# YOTSUBA_MC_ver_2_0.net
KiCad netlist of a schematic drawn in EAGLE
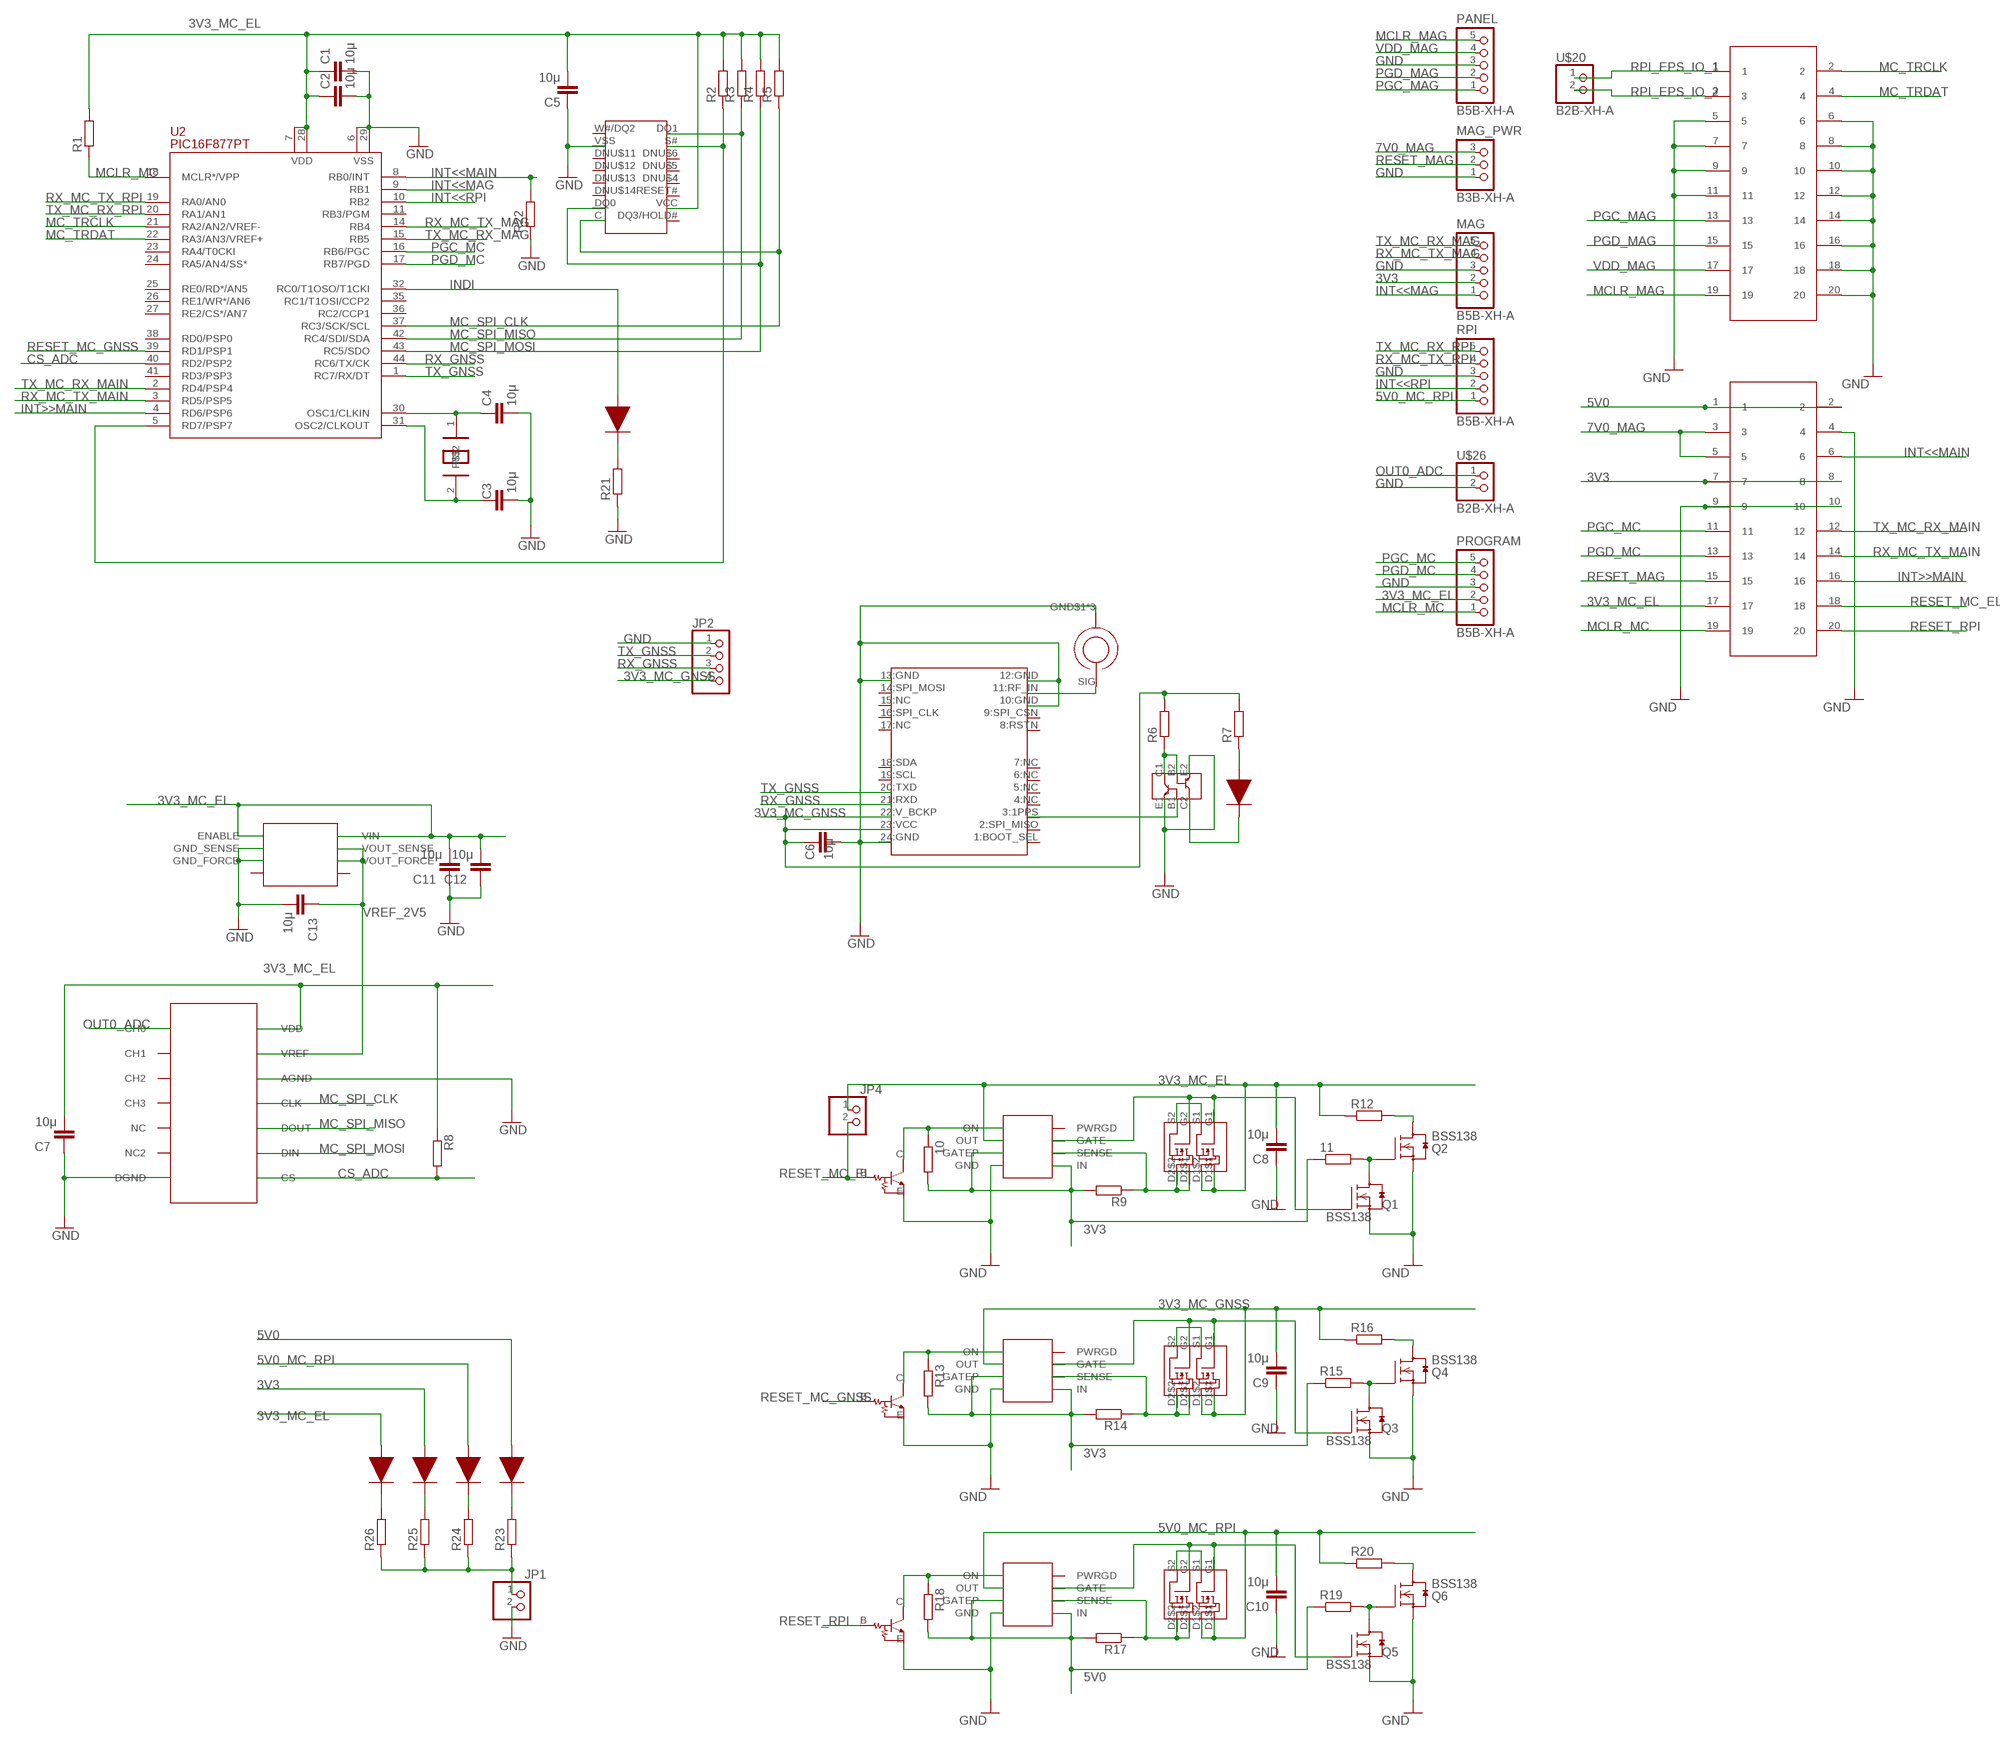
[diagram p0: schematic, sheet 1]

(export (version "E")
  (design (tool "Eeschema 10.0.6"))
  (components
    (comp (ref "10")
      (value "R-EU_M2012")
      (footprint "eagle-import:M2012")
      (libsource (lib "eagle-import") (part "R-EU_M2012"))
    )
    (comp (ref "11")
      (value "R-EU_M2012")
      (footprint "eagle-import:M2012")
      (libsource (lib "eagle-import") (part "R-EU_M2012"))
    )
    (comp (ref "C1")
      (value "10μ")
      (footprint "eagle-import:C2012")
      (libsource (lib "eagle-import") (part "C-EUC2012"))
    )
    (comp (ref "C2")
      (value "10μ")
      (footprint "eagle-import:C2012")
      (libsource (lib "eagle-import") (part "C-EUC2012"))
    )
    (comp (ref "C3")
      (value "10μ")
      (footprint "eagle-import:C2012")
      (libsource (lib "eagle-import") (part "C-EUC2012"))
    )
    (comp (ref "C4")
      (value "10μ")
      (footprint "eagle-import:C2012")
      (libsource (lib "eagle-import") (part "C-EUC2012"))
    )
    (comp (ref "C5")
      (value "10μ")
      (footprint "eagle-import:C2012")
      (libsource (lib "eagle-import") (part "C-EUC2012"))
    )
    (comp (ref "C6")
      (value "10μ")
      (footprint "eagle-import:C2012")
      (libsource (lib "eagle-import") (part "C-EUC2012"))
    )
    (comp (ref "C7")
      (value "10μ")
      (footprint "eagle-import:C2012")
      (libsource (lib "eagle-import") (part "C-EUC2012"))
    )
    (comp (ref "C8")
      (value "10μ")
      (footprint "eagle-import:C2012")
      (libsource (lib "eagle-import") (part "C-EUC2012"))
    )
    (comp (ref "C9")
      (value "10μ")
      (footprint "eagle-import:C2012")
      (libsource (lib "eagle-import") (part "C-EUC2012"))
    )
    (comp (ref "C10")
      (value "10μ")
      (footprint "eagle-import:C2012")
      (libsource (lib "eagle-import") (part "C-EUC2012"))
    )
    (comp (ref "C11")
      (value "10μ")
      (footprint "eagle-import:C2012")
      (libsource (lib "eagle-import") (part "C-EUC2012"))
    )
    (comp (ref "C12")
      (value "10μ")
      (footprint "eagle-import:C2012")
      (libsource (lib "eagle-import") (part "C-EUC2012"))
    )
    (comp (ref "C13")
      (value "10μ")
      (footprint "eagle-import:C2012")
      (libsource (lib "eagle-import") (part "C-EUC2012"))
    )
    (comp (ref "CLK1")
      (value "HC49/4H")
      (footprint "eagle-import:HC49_4H")
      (libsource (lib "eagle-import") (part "HC49/4H"))
    )
    (comp (ref "JP1")
      (value "PINHD-1X2")
      (footprint "eagle-import:1X02")
      (libsource (lib "eagle-import") (part "PINHD-1X2"))
    )
    (comp (ref "JP2")
      (value "PINHD-1X4")
      (footprint "eagle-import:1X04")
      (libsource (lib "eagle-import") (part "PINHD-1X4"))
    )
    (comp (ref "JP4")
      (value "PINHD-1X2")
      (footprint "eagle-import:1X02")
      (libsource (lib "eagle-import") (part "PINHD-1X2"))
    )
    (comp (ref "MAG")
      (value "B5B-XH-A")
      (footprint "eagle-import:B5B-XH-A")
      (libsource (lib "eagle-import") (part "B5B-XH-A"))
    )
    (comp (ref "MAG_PWR")
      (value "B3B-XH-A")
      (footprint "eagle-import:B3B-XH-A")
      (libsource (lib "eagle-import") (part "B3B-XH-A"))
    )
    (comp (ref "PANEL")
      (value "B5B-XH-A")
      (footprint "eagle-import:B5B-XH-A")
      (libsource (lib "eagle-import") (part "B5B-XH-A"))
    )
    (comp (ref "PROGRAM")
      (value "B5B-XH-A")
      (footprint "eagle-import:B5B-XH-A")
      (libsource (lib "eagle-import") (part "B5B-XH-A"))
    )
    (comp (ref "Q1")
      (value "BSS138")
      (footprint "eagle-import:SOT23")
      (libsource (lib "eagle-import") (part "BSS138"))
    )
    (comp (ref "Q2")
      (value "BSS138")
      (footprint "eagle-import:SOT23")
      (libsource (lib "eagle-import") (part "BSS138"))
    )
    (comp (ref "Q3")
      (value "BSS138")
      (footprint "eagle-import:SOT23")
      (libsource (lib "eagle-import") (part "BSS138"))
    )
    (comp (ref "Q4")
      (value "BSS138")
      (footprint "eagle-import:SOT23")
      (libsource (lib "eagle-import") (part "BSS138"))
    )
    (comp (ref "Q5")
      (value "BSS138")
      (footprint "eagle-import:SOT23")
      (libsource (lib "eagle-import") (part "BSS138"))
    )
    (comp (ref "Q6")
      (value "BSS138")
      (footprint "eagle-import:SOT23")
      (libsource (lib "eagle-import") (part "BSS138"))
    )
    (comp (ref "R1")
      (value "R-EU_M2012")
      (footprint "eagle-import:M2012")
      (libsource (lib "eagle-import") (part "R-EU_M2012"))
    )
    (comp (ref "R2")
      (value "R-EU_M2012")
      (footprint "eagle-import:M2012")
      (libsource (lib "eagle-import") (part "R-EU_M2012"))
    )
    (comp (ref "R3")
      (value "R-EU_M2012")
      (footprint "eagle-import:M2012")
      (libsource (lib "eagle-import") (part "R-EU_M2012"))
    )
    (comp (ref "R4")
      (value "R-EU_M2012")
      (footprint "eagle-import:M2012")
      (libsource (lib "eagle-import") (part "R-EU_M2012"))
    )
    (comp (ref "R5")
      (value "R-EU_M2012")
      (footprint "eagle-import:M2012")
      (libsource (lib "eagle-import") (part "R-EU_M2012"))
    )
    (comp (ref "R6")
      (value "R-EU_M2012")
      (footprint "eagle-import:M2012")
      (libsource (lib "eagle-import") (part "R-EU_M2012"))
    )
    (comp (ref "R7")
      (value "R-EU_M2012")
      (footprint "eagle-import:M2012")
      (libsource (lib "eagle-import") (part "R-EU_M2012"))
    )
    (comp (ref "R8")
      (value "R-EU_M2012")
      (footprint "eagle-import:M2012")
      (libsource (lib "eagle-import") (part "R-EU_M2012"))
    )
    (comp (ref "R9")
      (value "R-EU_M2012")
      (footprint "eagle-import:M2012")
      (libsource (lib "eagle-import") (part "R-EU_M2012"))
    )
    (comp (ref "R12")
      (value "R-EU_M2012")
      (footprint "eagle-import:M2012")
      (libsource (lib "eagle-import") (part "R-EU_M2012"))
    )
    (comp (ref "R13")
      (value "R-EU_M2012")
      (footprint "eagle-import:M2012")
      (libsource (lib "eagle-import") (part "R-EU_M2012"))
    )
    (comp (ref "R14")
      (value "R-EU_M2012")
      (footprint "eagle-import:M2012")
      (libsource (lib "eagle-import") (part "R-EU_M2012"))
    )
    (comp (ref "R15")
      (value "R-EU_M2012")
      (footprint "eagle-import:M2012")
      (libsource (lib "eagle-import") (part "R-EU_M2012"))
    )
    (comp (ref "R16")
      (value "R-EU_M2012")
      (footprint "eagle-import:M2012")
      (libsource (lib "eagle-import") (part "R-EU_M2012"))
    )
    (comp (ref "R17")
      (value "R-EU_M2012")
      (footprint "eagle-import:M2012")
      (libsource (lib "eagle-import") (part "R-EU_M2012"))
    )
    (comp (ref "R18")
      (value "R-EU_M2012")
      (footprint "eagle-import:M2012")
      (libsource (lib "eagle-import") (part "R-EU_M2012"))
    )
    (comp (ref "R19")
      (value "R-EU_M2012")
      (footprint "eagle-import:M2012")
      (libsource (lib "eagle-import") (part "R-EU_M2012"))
    )
    (comp (ref "R20")
      (value "R-EU_M2012")
      (footprint "eagle-import:M2012")
      (libsource (lib "eagle-import") (part "R-EU_M2012"))
    )
    (comp (ref "R21")
      (value "R-EU_M2012")
      (footprint "eagle-import:M2012")
      (libsource (lib "eagle-import") (part "R-EU_M2012"))
    )
    (comp (ref "R22")
      (value "R-EU_M2012")
      (footprint "eagle-import:M2012")
      (libsource (lib "eagle-import") (part "R-EU_M2012"))
    )
    (comp (ref "R23")
      (value "R-EU_M2012")
      (footprint "eagle-import:M2012")
      (libsource (lib "eagle-import") (part "R-EU_M2012"))
    )
    (comp (ref "R24")
      (value "R-EU_M2012")
      (footprint "eagle-import:M2012")
      (libsource (lib "eagle-import") (part "R-EU_M2012"))
    )
    (comp (ref "R25")
      (value "R-EU_M2012")
      (footprint "eagle-import:M2012")
      (libsource (lib "eagle-import") (part "R-EU_M2012"))
    )
    (comp (ref "R26")
      (value "R-EU_M2012")
      (footprint "eagle-import:M2012")
      (libsource (lib "eagle-import") (part "R-EU_M2012"))
    )
    (comp (ref "RPI")
      (value "B5B-XH-A")
      (footprint "eagle-import:B5B-XH-A")
      (libsource (lib "eagle-import") (part "B5B-XH-A"))
    )
    (comp (ref "U$1")
      (value "MT25QL512_16SOP2")
      (footprint "eagle-import:SOIC127P1032X265-16N")
      (libsource (lib "eagle-import") (part "MT25QL512_16SOP2"))
    )
    (comp (ref "U$2")
      (value "ORION_B16")
      (footprint "eagle-import:ORION_B16")
      (libsource (lib "eagle-import") (part "ORION_B16"))
    )
    (comp (ref "U$3")
      (value "HN1C01FU")
      (footprint "eagle-import:SOT65P210X100-6N")
      (libsource (lib "eagle-import") (part "HN1C01FU"))
    )
    (comp (ref "U$4")
      (value "LED_1608")
      (footprint "eagle-import:LED_1608")
      (libsource (lib "eagle-import") (part "LED_1608"))
    )
    (comp (ref "U$5")
      (value "U.FL-R")
      (footprint "eagle-import:U.FL-R")
      (libsource (lib "eagle-import") (part "U.FL-R"))
    )
    (comp (ref "U$6")
      (value "MCP3204_S")
      (footprint "eagle-import:MCP3204_S")
      (libsource (lib "eagle-import") (part "MCP3204_S"))
    )
    (comp (ref "U$7")
      (value "DMG6898LSD")
      (footprint "eagle-import:SOIC127P600X150-8N")
      (libsource (lib "eagle-import") (part "DMG6898LSD"))
    )
    (comp (ref "U$8")
      (value "LTC4361")
      (footprint "eagle-import:SOP65P280X100-8N")
      (libsource (lib "eagle-import") (part "LTC4361"))
    )
    (comp (ref "U$9")
      (value "DTC144EKA")
      (footprint "eagle-import:SOT-346")
      (libsource (lib "eagle-import") (part "DTC144EKA"))
    )
    (comp (ref "U$10")
      (value "DMG6898LSD")
      (footprint "eagle-import:SOIC127P600X150-8N")
      (libsource (lib "eagle-import") (part "DMG6898LSD"))
    )
    (comp (ref "U$11")
      (value "LTC4361")
      (footprint "eagle-import:SOP65P280X100-8N")
      (libsource (lib "eagle-import") (part "LTC4361"))
    )
    (comp (ref "U$12")
      (value "DTC144EKA")
      (footprint "eagle-import:SOT-346")
      (libsource (lib "eagle-import") (part "DTC144EKA"))
    )
    (comp (ref "U$13")
      (value "DMG6898LSD")
      (footprint "eagle-import:SOIC127P600X150-8N")
      (libsource (lib "eagle-import") (part "DMG6898LSD"))
    )
    (comp (ref "U$14")
      (value "LTC4361")
      (footprint "eagle-import:SOP65P280X100-8N")
      (libsource (lib "eagle-import") (part "LTC4361"))
    )
    (comp (ref "U$15")
      (value "DTC144EKA")
      (footprint "eagle-import:SOT-346")
      (libsource (lib "eagle-import") (part "DTC144EKA"))
    )
    (comp (ref "U$17")
      (value "M50-3001045")
      (footprint "eagle-import:M50-3001045")
      (libsource (lib "eagle-import") (part "M50-3001045"))
    )
    (comp (ref "U$18")
      (value "LED_1608")
      (footprint "eagle-import:LED_1608")
      (libsource (lib "eagle-import") (part "LED_1608"))
    )
    (comp (ref "U$19")
      (value "ADR35XX")
      (footprint "eagle-import:SOP65P490X110-8N")
      (libsource (lib "eagle-import") (part "ADR35XX"))
    )
    (comp (ref "U$20")
      (value "B2B-XH-A")
      (footprint "eagle-import:B2B-XH-A")
      (libsource (lib "eagle-import") (part "B2B-XH-A"))
    )
    (comp (ref "U$21")
      (value "LED_1608")
      (footprint "eagle-import:LED_1608")
      (libsource (lib "eagle-import") (part "LED_1608"))
    )
    (comp (ref "U$22")
      (value "M50-3001045")
      (footprint "eagle-import:M50-3001045")
      (libsource (lib "eagle-import") (part "M50-3001045"))
    )
    (comp (ref "U$23")
      (value "LED_1608")
      (footprint "eagle-import:LED_1608")
      (libsource (lib "eagle-import") (part "LED_1608"))
    )
    (comp (ref "U$24")
      (value "LED_1608")
      (footprint "eagle-import:LED_1608")
      (libsource (lib "eagle-import") (part "LED_1608"))
    )
    (comp (ref "U$25")
      (value "LED_1608")
      (footprint "eagle-import:LED_1608")
      (libsource (lib "eagle-import") (part "LED_1608"))
    )
    (comp (ref "U$26")
      (value "B2B-XH-A")
      (footprint "eagle-import:B2B-XH-A")
      (libsource (lib "eagle-import") (part "B2B-XH-A"))
    )
    (comp (ref "U2")
      (value "PIC16F877PT")
      (footprint "eagle-import:TQFP44")
      (libsource (lib "eagle-import") (part "PIC16F877PT"))
    )
  )
  (nets
    (net (code "1") (name "/3V3") (class "Default")
      (node (ref "10") (pin "2") (pinfunction "2_2") (pintype "passive"))
      (node (ref "11") (pin "1") (pinfunction "1_1") (pintype "passive"))
      (node (ref "MAG") (pin "2") (pinfunction "2_2") (pintype "passive"))
      (node (ref "R13") (pin "2") (pinfunction "2_2") (pintype "passive"))
      (node (ref "R14") (pin "2") (pinfunction "2_2") (pintype "passive"))
      (node (ref "R15") (pin "1") (pinfunction "1_1") (pintype "passive"))
      (node (ref "R9") (pin "2") (pinfunction "2_2") (pintype "passive"))
      (node (ref "U$11") (pin "GATEP") (pinfunction "GATEP_GATEP") (pintype "bidirectional"))
      (node (ref "U$11") (pin "IN") (pinfunction "IN_IN") (pintype "bidirectional"))
      (node (ref "U$17") (pin "7") (pinfunction "7_7") (pintype "bidirectional"))
      (node (ref "U$17") (pin "8") (pinfunction "8_8") (pintype "bidirectional"))
      (node (ref "U$24") (pin "A") (pinfunction "A_A") (pintype "bidirectional"))
      (node (ref "U$8") (pin "GATEP") (pinfunction "GATEP_GATEP") (pintype "bidirectional"))
      (node (ref "U$8") (pin "IN") (pinfunction "IN_IN") (pintype "bidirectional"))
    )
    (net (code "2") (name "/3V3_MC_EL") (class "Default")
      (node (ref "C1") (pin "1") (pinfunction "1_1") (pintype "passive"))
      (node (ref "C11") (pin "2") (pinfunction "2_2") (pintype "passive"))
      (node (ref "C12") (pin "2") (pinfunction "2_2") (pintype "passive"))
      (node (ref "C2") (pin "1") (pinfunction "1_1") (pintype "passive"))
      (node (ref "C5") (pin "2") (pinfunction "2_2") (pintype "passive"))
      (node (ref "C7") (pin "2") (pinfunction "2_2") (pintype "passive"))
      (node (ref "C8") (pin "2") (pinfunction "2_2") (pintype "passive"))
      (node (ref "JP4") (pin "1") (pinfunction "1_1") (pintype "passive"))
      (node (ref "PROGRAM") (pin "2") (pinfunction "2_2") (pintype "passive"))
      (node (ref "R1") (pin "2") (pinfunction "2_2") (pintype "passive"))
      (node (ref "R12") (pin "1") (pinfunction "1_1") (pintype "passive"))
      (node (ref "R2") (pin "2") (pinfunction "2_2") (pintype "passive"))
      (node (ref "R3") (pin "2") (pinfunction "2_2") (pintype "passive"))
      (node (ref "R4") (pin "2") (pinfunction "2_2") (pintype "passive"))
      (node (ref "R5") (pin "2") (pinfunction "2_2") (pintype "passive"))
      (node (ref "R8") (pin "1") (pinfunction "1_1") (pintype "passive"))
      (node (ref "U$1") (pin "VCC") (pinfunction "VCC_VCC") (pintype "bidirectional"))
      (node (ref "U$17") (pin "17") (pinfunction "17_17") (pintype "bidirectional"))
      (node (ref "U$19") (pin "ENABLE") (pinfunction "ENABLE_ENABLE") (pintype "bidirectional"))
      (node (ref "U$19") (pin "VIN") (pinfunction "VIN_VIN") (pintype "bidirectional"))
      (node (ref "U$25") (pin "A") (pinfunction "A_A") (pintype "bidirectional"))
      (node (ref "U$6") (pin "VDD") (pinfunction "VDD_VDD") (pintype "bidirectional"))
      (node (ref "U$7") (pin "D1$1") (pinfunction "D1$1_D1$1") (pintype "bidirectional"))
      (node (ref "U$7") (pin "D1$2") (pinfunction "D1$2_D1$2") (pintype "bidirectional"))
      (node (ref "U$8") (pin "OUT") (pinfunction "OUT_OUT") (pintype "bidirectional"))
      (node (ref "U2") (pin "28") (pinfunction "VDD_28") (pintype "bidirectional"))
      (node (ref "U2") (pin "7") (pinfunction "VDD_7") (pintype "bidirectional"))
    )
    (net (code "3") (name "/3V3_MC_GNSS") (class "Default")
      (node (ref "C6") (pin "1") (pinfunction "1_1") (pintype "passive"))
      (node (ref "C9") (pin "2") (pinfunction "2_2") (pintype "passive"))
      (node (ref "JP2") (pin "4") (pinfunction "4_4") (pintype "passive"))
      (node (ref "R16") (pin "1") (pinfunction "1_1") (pintype "passive"))
      (node (ref "R6") (pin "2") (pinfunction "2_2") (pintype "passive"))
      (node (ref "R7") (pin "2") (pinfunction "2_2") (pintype "passive"))
      (node (ref "U$10") (pin "D1$1") (pinfunction "D1$1_D1$1") (pintype "bidirectional"))
      (node (ref "U$10") (pin "D1$2") (pinfunction "D1$2_D1$2") (pintype "bidirectional"))
      (node (ref "U$11") (pin "OUT") (pinfunction "OUT_OUT") (pintype "bidirectional"))
      (node (ref "U$2") (pin "22:V_BCKP") (pinfunction "22:V_BCKP_22:V_BCKP") (pintype "bidirectional"))
      (node (ref "U$2") (pin "23:VCC") (pinfunction "23:VCC_23:VCC") (pintype "bidirectional"))
    )
    (net (code "4") (name "/5V0") (class "Default")
      (node (ref "R17") (pin "2") (pinfunction "2_2") (pintype "passive"))
      (node (ref "R18") (pin "2") (pinfunction "2_2") (pintype "passive"))
      (node (ref "R19") (pin "1") (pinfunction "1_1") (pintype "passive"))
      (node (ref "U$14") (pin "GATEP") (pinfunction "GATEP_GATEP") (pintype "bidirectional"))
      (node (ref "U$14") (pin "IN") (pinfunction "IN_IN") (pintype "bidirectional"))
      (node (ref "U$17") (pin "1") (pinfunction "1_1") (pintype "bidirectional"))
      (node (ref "U$17") (pin "2") (pinfunction "2_2") (pintype "bidirectional"))
      (node (ref "U$21") (pin "A") (pinfunction "A_A") (pintype "bidirectional"))
    )
    (net (code "5") (name "/5V0_MC_RPI") (class "Default")
      (node (ref "C10") (pin "2") (pinfunction "2_2") (pintype "passive"))
      (node (ref "R20") (pin "1") (pinfunction "1_1") (pintype "passive"))
      (node (ref "RPI") (pin "1") (pinfunction "1_1") (pintype "passive"))
      (node (ref "U$13") (pin "D1$1") (pinfunction "D1$1_D1$1") (pintype "bidirectional"))
      (node (ref "U$13") (pin "D1$2") (pinfunction "D1$2_D1$2") (pintype "bidirectional"))
      (node (ref "U$14") (pin "OUT") (pinfunction "OUT_OUT") (pintype "bidirectional"))
      (node (ref "U$23") (pin "A") (pinfunction "A_A") (pintype "bidirectional"))
    )
    (net (code "6") (name "/7V0_MAG") (class "Default")
      (node (ref "MAG_PWR") (pin "3") (pinfunction "3_3") (pintype "passive"))
      (node (ref "U$17") (pin "3") (pinfunction "3_3") (pintype "bidirectional"))
      (node (ref "U$17") (pin "5") (pinfunction "5_5") (pintype "bidirectional"))
    )
    (net (code "7") (name "/CS_ADC") (class "Default")
      (node (ref "R8") (pin "2") (pinfunction "2_2") (pintype "passive"))
      (node (ref "U$6") (pin "CS") (pinfunction "CS_CS") (pintype "bidirectional"))
      (node (ref "U2") (pin "40") (pinfunction "RD2/PSP2_40") (pintype "bidirectional"))
    )
    (net (code "8") (name "/INDI") (class "Default")
      (node (ref "U$18") (pin "A") (pinfunction "A_A") (pintype "bidirectional"))
      (node (ref "U2") (pin "32") (pinfunction "RC0/T1OSO/T1CKI_32") (pintype "bidirectional"))
    )
    (net (code "9") (name "/INT<<MAG") (class "Default")
      (node (ref "MAG") (pin "1") (pinfunction "1_1") (pintype "passive"))
      (node (ref "U2") (pin "9") (pinfunction "RB1_9") (pintype "bidirectional"))
    )
    (net (code "10") (name "/INT<<MAIN") (class "Default")
      (node (ref "R22") (pin "2") (pinfunction "2_2") (pintype "passive"))
      (node (ref "U$17") (pin "6") (pinfunction "6_6") (pintype "bidirectional"))
      (node (ref "U2") (pin "8") (pinfunction "RB0/INT_8") (pintype "bidirectional"))
    )
    (net (code "11") (name "/INT<<RPI") (class "Default")
      (node (ref "RPI") (pin "2") (pinfunction "2_2") (pintype "passive"))
      (node (ref "U2") (pin "10") (pinfunction "RB2_10") (pintype "bidirectional"))
    )
    (net (code "12") (name "/INT>>MAIN") (class "Default")
      (node (ref "U$17") (pin "16") (pinfunction "16_16") (pintype "bidirectional"))
      (node (ref "U2") (pin "4") (pinfunction "RD6/PSP6_4") (pintype "bidirectional"))
    )
    (net (code "13") (name "/MCLR_MAG") (class "Default")
      (node (ref "PANEL") (pin "5") (pinfunction "5_5") (pintype "passive"))
      (node (ref "U$22") (pin "19") (pinfunction "19_19") (pintype "bidirectional"))
    )
    (net (code "14") (name "/MCLR_MC") (class "Default")
      (node (ref "PROGRAM") (pin "1") (pinfunction "1_1") (pintype "passive"))
      (node (ref "R1") (pin "1") (pinfunction "1_1") (pintype "passive"))
      (node (ref "U$17") (pin "19") (pinfunction "19_19") (pintype "bidirectional"))
      (node (ref "U2") (pin "18") (pinfunction "MCLR*/VPP_18") (pintype "input"))
    )
    (net (code "15") (name "/MC_SPI_CLK") (class "Default")
      (node (ref "R5") (pin "1") (pinfunction "1_1") (pintype "passive"))
      (node (ref "U$1") (pin "C") (pinfunction "C_C") (pintype "bidirectional"))
      (node (ref "U$6") (pin "CLK") (pinfunction "CLK_CLK") (pintype "bidirectional"))
      (node (ref "U2") (pin "37") (pinfunction "RC3/SCK/SCL_37") (pintype "bidirectional"))
    )
    (net (code "16") (name "/MC_SPI_MISO") (class "Default")
      (node (ref "R3") (pin "1") (pinfunction "1_1") (pintype "passive"))
      (node (ref "U$1") (pin "DQ1") (pinfunction "DQ1_DQ1") (pintype "bidirectional"))
      (node (ref "U$6") (pin "DOUT") (pinfunction "DOUT_DOUT") (pintype "bidirectional"))
      (node (ref "U2") (pin "42") (pinfunction "RC4/SDI/SDA_42") (pintype "bidirectional"))
    )
    (net (code "17") (name "/MC_SPI_MOSI") (class "Default")
      (node (ref "R4") (pin "1") (pinfunction "1_1") (pintype "passive"))
      (node (ref "U$1") (pin "DQ0") (pinfunction "DQ0_DQ0") (pintype "bidirectional"))
      (node (ref "U$6") (pin "DIN") (pinfunction "DIN_DIN") (pintype "bidirectional"))
      (node (ref "U2") (pin "43") (pinfunction "RC5/SDO_43") (pintype "bidirectional"))
    )
    (net (code "18") (name "/MC_TRCLK") (class "Default")
      (node (ref "U$22") (pin "2") (pinfunction "2_2") (pintype "bidirectional"))
      (node (ref "U2") (pin "21") (pinfunction "RA2/AN2/VREF-_21") (pintype "bidirectional"))
    )
    (net (code "19") (name "/MC_TRDAT") (class "Default")
      (node (ref "U$22") (pin "4") (pinfunction "4_4") (pintype "bidirectional"))
      (node (ref "U2") (pin "22") (pinfunction "RA3/AN3/VREF+_22") (pintype "bidirectional"))
    )
    (net (code "20") (name "/OUT0_ADC") (class "Default")
      (node (ref "U$26") (pin "1") (pinfunction "1_1") (pintype "passive"))
      (node (ref "U$6") (pin "CH0") (pinfunction "CH0_CH0") (pintype "bidirectional"))
    )
    (net (code "21") (name "/PGC_MAG") (class "Default")
      (node (ref "PANEL") (pin "1") (pinfunction "1_1") (pintype "passive"))
      (node (ref "U$22") (pin "13") (pinfunction "13_13") (pintype "bidirectional"))
    )
    (net (code "22") (name "/PGC_MC") (class "Default")
      (node (ref "PROGRAM") (pin "5") (pinfunction "5_5") (pintype "passive"))
      (node (ref "U$17") (pin "11") (pinfunction "11_11") (pintype "bidirectional"))
      (node (ref "U2") (pin "16") (pinfunction "RB6/PGC_16") (pintype "bidirectional"))
    )
    (net (code "23") (name "/PGD_MAG") (class "Default")
      (node (ref "PANEL") (pin "2") (pinfunction "2_2") (pintype "passive"))
      (node (ref "U$22") (pin "15") (pinfunction "15_15") (pintype "bidirectional"))
    )
    (net (code "24") (name "/PGD_MC") (class "Default")
      (node (ref "PROGRAM") (pin "4") (pinfunction "4_4") (pintype "passive"))
      (node (ref "U$17") (pin "13") (pinfunction "13_13") (pintype "bidirectional"))
      (node (ref "U2") (pin "17") (pinfunction "RB7/PGD_17") (pintype "bidirectional"))
    )
    (net (code "25") (name "/RESET_MAG") (class "Default")
      (node (ref "MAG_PWR") (pin "2") (pinfunction "2_2") (pintype "passive"))
      (node (ref "U$17") (pin "15") (pinfunction "15_15") (pintype "bidirectional"))
    )
    (net (code "26") (name "/RESET_MC_EL") (class "Default")
      (node (ref "JP4") (pin "2") (pinfunction "2_2") (pintype "passive"))
      (node (ref "U$17") (pin "18") (pinfunction "18_18") (pintype "bidirectional"))
      (node (ref "U$9") (pin "B") (pinfunction "B_B") (pintype "bidirectional"))
    )
    (net (code "27") (name "/RESET_MC_GNSS") (class "Default")
      (node (ref "U$12") (pin "B") (pinfunction "B_B") (pintype "bidirectional"))
      (node (ref "U2") (pin "39") (pinfunction "RD1/PSP1_39") (pintype "bidirectional"))
    )
    (net (code "28") (name "/RESET_RPI") (class "Default")
      (node (ref "U$15") (pin "B") (pinfunction "B_B") (pintype "bidirectional"))
      (node (ref "U$17") (pin "20") (pinfunction "20_20") (pintype "bidirectional"))
    )
    (net (code "29") (name "/RPI_EPS_IO_1") (class "Default")
      (node (ref "U$20") (pin "1") (pinfunction "1_1") (pintype "passive"))
      (node (ref "U$22") (pin "1") (pinfunction "1_1") (pintype "bidirectional"))
    )
    (net (code "30") (name "/RPI_EPS_IO_2") (class "Default")
      (node (ref "U$20") (pin "2") (pinfunction "2_2") (pintype "passive"))
      (node (ref "U$22") (pin "3") (pinfunction "3_3") (pintype "bidirectional"))
    )
    (net (code "31") (name "/RX_GNSS") (class "Default")
      (node (ref "JP2") (pin "3") (pinfunction "3_3") (pintype "passive"))
      (node (ref "U$2") (pin "21:RXD") (pinfunction "21:RXD_21:RXD") (pintype "bidirectional"))
      (node (ref "U2") (pin "44") (pinfunction "RC6/TX/CK_44") (pintype "bidirectional"))
    )
    (net (code "32") (name "/RX_MC_TX_MAG") (class "Default")
      (node (ref "MAG") (pin "4") (pinfunction "4_4") (pintype "passive"))
      (node (ref "U2") (pin "14") (pinfunction "RB4_14") (pintype "bidirectional"))
    )
    (net (code "33") (name "/RX_MC_TX_MAIN") (class "Default")
      (node (ref "U$17") (pin "14") (pinfunction "14_14") (pintype "bidirectional"))
      (node (ref "U2") (pin "3") (pinfunction "RD5/PSP5_3") (pintype "bidirectional"))
    )
    (net (code "34") (name "/RX_MC_TX_RPI") (class "Default")
      (node (ref "RPI") (pin "4") (pinfunction "4_4") (pintype "passive"))
      (node (ref "U2") (pin "19") (pinfunction "RA0/AN0_19") (pintype "bidirectional"))
    )
    (net (code "35") (name "/TX_GNSS") (class "Default")
      (node (ref "JP2") (pin "2") (pinfunction "2_2") (pintype "passive"))
      (node (ref "U$2") (pin "20:TXD") (pinfunction "20:TXD_20:TXD") (pintype "bidirectional"))
      (node (ref "U2") (pin "1") (pinfunction "RC7/RX/DT_1") (pintype "bidirectional"))
    )
    (net (code "36") (name "/TX_MC_RX_MAG") (class "Default")
      (node (ref "MAG") (pin "5") (pinfunction "5_5") (pintype "passive"))
      (node (ref "U2") (pin "15") (pinfunction "RB5_15") (pintype "bidirectional"))
    )
    (net (code "37") (name "/TX_MC_RX_MAIN") (class "Default")
      (node (ref "U$17") (pin "12") (pinfunction "12_12") (pintype "bidirectional"))
      (node (ref "U2") (pin "2") (pinfunction "RD4/PSP4_2") (pintype "bidirectional"))
    )
    (net (code "38") (name "/TX_MC_RX_RPI") (class "Default")
      (node (ref "RPI") (pin "5") (pinfunction "5_5") (pintype "passive"))
      (node (ref "U2") (pin "20") (pinfunction "RA1/AN1_20") (pintype "bidirectional"))
    )
    (net (code "39") (name "/VDD_MAG") (class "Default")
      (node (ref "PANEL") (pin "4") (pinfunction "4_4") (pintype "passive"))
      (node (ref "U$22") (pin "17") (pinfunction "17_17") (pintype "bidirectional"))
    )
    (net (code "40") (name "/VREF_2V5") (class "Default")
      (node (ref "C13") (pin "1") (pinfunction "1_1") (pintype "passive"))
      (node (ref "U$19") (pin "VOUT_FORCE") (pinfunction "VOUT_FORCE_VOUT_FORCE") (pintype "bidirectional"))
      (node (ref "U$19") (pin "VOUT_SENSE") (pinfunction "VOUT_SENSE_VOUT_SENSE") (pintype "bidirectional"))
      (node (ref "U$6") (pin "VREF") (pinfunction "VREF_VREF") (pintype "bidirectional"))
    )
    (net (code "41") (name "GND") (class "Default")
      (node (ref "C1") (pin "2") (pinfunction "2_2") (pintype "passive"))
      (node (ref "C10") (pin "1") (pinfunction "1_1") (pintype "passive"))
      (node (ref "C11") (pin "1") (pinfunction "1_1") (pintype "passive"))
      (node (ref "C12") (pin "1") (pinfunction "1_1") (pintype "passive"))
      (node (ref "C13") (pin "2") (pinfunction "2_2") (pintype "passive"))
      (node (ref "C2") (pin "2") (pinfunction "2_2") (pintype "passive"))
      (node (ref "C3") (pin "2") (pinfunction "2_2") (pintype "passive"))
      (node (ref "C4") (pin "2") (pinfunction "2_2") (pintype "passive"))
      (node (ref "C5") (pin "1") (pinfunction "1_1") (pintype "passive"))
      (node (ref "C6") (pin "2") (pinfunction "2_2") (pintype "passive"))
      (node (ref "C7") (pin "1") (pinfunction "1_1") (pintype "passive"))
      (node (ref "C8") (pin "1") (pinfunction "1_1") (pintype "passive"))
      (node (ref "C9") (pin "1") (pinfunction "1_1") (pintype "passive"))
      (node (ref "JP1") (pin "2") (pinfunction "2_2") (pintype "passive"))
      (node (ref "JP2") (pin "1") (pinfunction "1_1") (pintype "passive"))
      (node (ref "MAG") (pin "3") (pinfunction "3_3") (pintype "passive"))
      (node (ref "MAG_PWR") (pin "1") (pinfunction "1_1") (pintype "passive"))
      (node (ref "PANEL") (pin "3") (pinfunction "3_3") (pintype "passive"))
      (node (ref "PROGRAM") (pin "3") (pinfunction "3_3") (pintype "passive"))
      (node (ref "Q1") (pin "2") (pinfunction "S_2") (pintype "passive"))
      (node (ref "Q2") (pin "2") (pinfunction "S_2") (pintype "passive"))
      (node (ref "Q3") (pin "2") (pinfunction "S_2") (pintype "passive"))
      (node (ref "Q4") (pin "2") (pinfunction "S_2") (pintype "passive"))
      (node (ref "Q5") (pin "2") (pinfunction "S_2") (pintype "passive"))
      (node (ref "Q6") (pin "2") (pinfunction "S_2") (pintype "passive"))
      (node (ref "R21") (pin "1") (pinfunction "1_1") (pintype "passive"))
      (node (ref "R22") (pin "1") (pinfunction "1_1") (pintype "passive"))
      (node (ref "RPI") (pin "3") (pinfunction "3_3") (pintype "passive"))
      (node (ref "U$1") (pin "VSS") (pinfunction "VSS_VSS") (pintype "bidirectional"))
      (node (ref "U$11") (pin "GND") (pinfunction "GND_GND") (pintype "bidirectional"))
      (node (ref "U$12") (pin "E") (pinfunction "E_E") (pintype "bidirectional"))
      (node (ref "U$14") (pin "GND") (pinfunction "GND_GND") (pintype "bidirectional"))
      (node (ref "U$15") (pin "E") (pinfunction "E_E") (pintype "bidirectional"))
      (node (ref "U$17") (pin "10") (pinfunction "10_10") (pintype "bidirectional"))
      (node (ref "U$17") (pin "4") (pinfunction "4_4") (pintype "bidirectional"))
      (node (ref "U$17") (pin "9") (pinfunction "9_9") (pintype "bidirectional"))
      (node (ref "U$19") (pin "GND_FORCE") (pinfunction "GND_FORCE_GND_FORCE") (pintype "bidirectional"))
      (node (ref "U$19") (pin "GND_SENSE") (pinfunction "GND_SENSE_GND_SENSE") (pintype "bidirectional"))
      (node (ref "U$2") (pin "10:GND") (pinfunction "10:GND_10:GND") (pintype "bidirectional"))
      (node (ref "U$2") (pin "12:GND") (pinfunction "12:GND_12:GND") (pintype "bidirectional"))
      (node (ref "U$2") (pin "13:GND") (pinfunction "13:GND_13:GND") (pintype "bidirectional"))
      (node (ref "U$2") (pin "24:GND") (pinfunction "24:GND_24:GND") (pintype "bidirectional"))
      (node (ref "U$22") (pin "10") (pinfunction "10_10") (pintype "bidirectional"))
      (node (ref "U$22") (pin "11") (pinfunction "11_11") (pintype "bidirectional"))
      (node (ref "U$22") (pin "12") (pinfunction "12_12") (pintype "bidirectional"))
      (node (ref "U$22") (pin "14") (pinfunction "14_14") (pintype "bidirectional"))
      (node (ref "U$22") (pin "16") (pinfunction "16_16") (pintype "bidirectional"))
      (node (ref "U$22") (pin "18") (pinfunction "18_18") (pintype "bidirectional"))
      (node (ref "U$22") (pin "20") (pinfunction "20_20") (pintype "bidirectional"))
      (node (ref "U$22") (pin "5") (pinfunction "5_5") (pintype "bidirectional"))
      (node (ref "U$22") (pin "6") (pinfunction "6_6") (pintype "bidirectional"))
      (node (ref "U$22") (pin "7") (pinfunction "7_7") (pintype "bidirectional"))
      (node (ref "U$22") (pin "8") (pinfunction "8_8") (pintype "bidirectional"))
      (node (ref "U$22") (pin "9") (pinfunction "9_9") (pintype "bidirectional"))
      (node (ref "U$26") (pin "2") (pinfunction "2_2") (pintype "passive"))
      (node (ref "U$3") (pin "E1") (pinfunction "E1_E1") (pintype "bidirectional"))
      (node (ref "U$3") (pin "E2") (pinfunction "E2_E2") (pintype "bidirectional"))
      (node (ref "U$5") (pin "GND$1") (pinfunction "GND_GND$1") (pintype "bidirectional"))
      (node (ref "U$5") (pin "GND$2") (pinfunction "GND_GND$2") (pintype "bidirectional"))
      (node (ref "U$5") (pin "GND$3") (pinfunction "GND_GND$3") (pintype "bidirectional"))
      (node (ref "U$6") (pin "AGND") (pinfunction "AGND_AGND") (pintype "bidirectional"))
      (node (ref "U$6") (pin "DGND") (pinfunction "DGND_DGND") (pintype "bidirectional"))
      (node (ref "U$8") (pin "GND") (pinfunction "GND_GND") (pintype "bidirectional"))
      (node (ref "U$9") (pin "E") (pinfunction "E_E") (pintype "bidirectional"))
      (node (ref "U2") (pin "29") (pinfunction "VSS_29") (pintype "bidirectional"))
      (node (ref "U2") (pin "6") (pinfunction "VSS_6") (pintype "bidirectional"))
    )
    (net (code "42") (name "Net-(10-Pad1)") (class "Default")
      (node (ref "10") (pin "1") (pinfunction "1_1") (pintype "passive"))
      (node (ref "U$8") (pin "ON") (pinfunction "ON_ON") (pintype "bidirectional"))
      (node (ref "U$9") (pin "C") (pinfunction "C_C") (pintype "bidirectional"))
    )
    (net (code "43") (name "Net-(CLK1-P$1)") (class "Default")
      (node (ref "C4") (pin "1") (pinfunction "1_1") (pintype "passive"))
      (node (ref "CLK1") (pin "1") (pinfunction "P$1_1") (pintype "bidirectional"))
      (node (ref "U2") (pin "30") (pinfunction "OSC1/CLKIN_30") (pintype "input"))
    )
    (net (code "44") (name "Net-(CLK1-P$2)") (class "Default")
      (node (ref "C3") (pin "1") (pinfunction "1_1") (pintype "passive"))
      (node (ref "CLK1") (pin "2") (pinfunction "P$2_2") (pintype "bidirectional"))
      (node (ref "U2") (pin "31") (pinfunction "OSC2/CLKOUT_31") (pintype "output"))
    )
    (net (code "45") (name "Net-(JP1-Pad1)") (class "Default")
      (node (ref "JP1") (pin "1") (pinfunction "1_1") (pintype "passive"))
      (node (ref "R23") (pin "1") (pinfunction "1_1") (pintype "passive"))
      (node (ref "R24") (pin "1") (pinfunction "1_1") (pintype "passive"))
      (node (ref "R25") (pin "1") (pinfunction "1_1") (pintype "passive"))
      (node (ref "R26") (pin "1") (pinfunction "1_1") (pintype "passive"))
    )
    (net (code "46") (name "Net-(Q1-D)") (class "Default")
      (node (ref "11") (pin "2") (pinfunction "2_2") (pintype "passive"))
      (node (ref "Q1") (pin "3") (pinfunction "D_3") (pintype "passive"))
      (node (ref "Q2") (pin "1") (pinfunction "G_1") (pintype "passive"))
    )
    (net (code "47") (name "Net-(Q1-G)") (class "Default")
      (node (ref "Q1") (pin "1") (pinfunction "G_1") (pintype "passive"))
      (node (ref "U$7") (pin "G1") (pinfunction "G1_G1") (pintype "bidirectional"))
      (node (ref "U$7") (pin "G2") (pinfunction "G2_G2") (pintype "bidirectional"))
      (node (ref "U$8") (pin "GATE") (pinfunction "GATE_GATE") (pintype "bidirectional"))
    )
    (net (code "48") (name "Net-(Q2-D)") (class "Default")
      (node (ref "Q2") (pin "3") (pinfunction "D_3") (pintype "passive"))
      (node (ref "R12") (pin "2") (pinfunction "2_2") (pintype "passive"))
    )
    (net (code "49") (name "Net-(Q3-D)") (class "Default")
      (node (ref "Q3") (pin "3") (pinfunction "D_3") (pintype "passive"))
      (node (ref "Q4") (pin "1") (pinfunction "G_1") (pintype "passive"))
      (node (ref "R15") (pin "2") (pinfunction "2_2") (pintype "passive"))
    )
    (net (code "50") (name "Net-(Q3-G)") (class "Default")
      (node (ref "Q3") (pin "1") (pinfunction "G_1") (pintype "passive"))
      (node (ref "U$10") (pin "G1") (pinfunction "G1_G1") (pintype "bidirectional"))
      (node (ref "U$10") (pin "G2") (pinfunction "G2_G2") (pintype "bidirectional"))
      (node (ref "U$11") (pin "GATE") (pinfunction "GATE_GATE") (pintype "bidirectional"))
    )
    (net (code "51") (name "Net-(Q4-D)") (class "Default")
      (node (ref "Q4") (pin "3") (pinfunction "D_3") (pintype "passive"))
      (node (ref "R16") (pin "2") (pinfunction "2_2") (pintype "passive"))
    )
    (net (code "52") (name "Net-(Q5-D)") (class "Default")
      (node (ref "Q5") (pin "3") (pinfunction "D_3") (pintype "passive"))
      (node (ref "Q6") (pin "1") (pinfunction "G_1") (pintype "passive"))
      (node (ref "R19") (pin "2") (pinfunction "2_2") (pintype "passive"))
    )
    (net (code "53") (name "Net-(Q5-G)") (class "Default")
      (node (ref "Q5") (pin "1") (pinfunction "G_1") (pintype "passive"))
      (node (ref "U$13") (pin "G1") (pinfunction "G1_G1") (pintype "bidirectional"))
      (node (ref "U$13") (pin "G2") (pinfunction "G2_G2") (pintype "bidirectional"))
      (node (ref "U$14") (pin "GATE") (pinfunction "GATE_GATE") (pintype "bidirectional"))
    )
    (net (code "54") (name "Net-(Q6-D)") (class "Default")
      (node (ref "Q6") (pin "3") (pinfunction "D_3") (pintype "passive"))
      (node (ref "R20") (pin "2") (pinfunction "2_2") (pintype "passive"))
    )
    (net (code "55") (name "Net-(R6-Pad1)") (class "Default")
      (node (ref "R6") (pin "1") (pinfunction "1_1") (pintype "passive"))
      (node (ref "U$3") (pin "B2") (pinfunction "B2_B2") (pintype "bidirectional"))
      (node (ref "U$3") (pin "C1") (pinfunction "C1_C1") (pintype "bidirectional"))
    )
    (net (code "56") (name "Net-(R7-Pad1)") (class "Default")
      (node (ref "R7") (pin "1") (pinfunction "1_1") (pintype "passive"))
      (node (ref "U$4") (pin "A") (pinfunction "A_A") (pintype "bidirectional"))
    )
    (net (code "57") (name "Net-(R9-Pad1)") (class "Default")
      (node (ref "R9") (pin "1") (pinfunction "1_1") (pintype "passive"))
      (node (ref "U$7") (pin "D2$1") (pinfunction "D2$1_D2$1") (pintype "bidirectional"))
      (node (ref "U$7") (pin "D2$2") (pinfunction "D2$2_D2$2") (pintype "bidirectional"))
      (node (ref "U$8") (pin "SENSE") (pinfunction "SENSE_SENSE") (pintype "bidirectional"))
    )
    (net (code "58") (name "Net-(R13-Pad1)") (class "Default")
      (node (ref "R13") (pin "1") (pinfunction "1_1") (pintype "passive"))
      (node (ref "U$11") (pin "ON") (pinfunction "ON_ON") (pintype "bidirectional"))
      (node (ref "U$12") (pin "C") (pinfunction "C_C") (pintype "bidirectional"))
    )
    (net (code "59") (name "Net-(R14-Pad1)") (class "Default")
      (node (ref "R14") (pin "1") (pinfunction "1_1") (pintype "passive"))
      (node (ref "U$10") (pin "D2$1") (pinfunction "D2$1_D2$1") (pintype "bidirectional"))
      (node (ref "U$10") (pin "D2$2") (pinfunction "D2$2_D2$2") (pintype "bidirectional"))
      (node (ref "U$11") (pin "SENSE") (pinfunction "SENSE_SENSE") (pintype "bidirectional"))
    )
    (net (code "60") (name "Net-(R17-Pad1)") (class "Default")
      (node (ref "R17") (pin "1") (pinfunction "1_1") (pintype "passive"))
      (node (ref "U$13") (pin "D2$1") (pinfunction "D2$1_D2$1") (pintype "bidirectional"))
      (node (ref "U$13") (pin "D2$2") (pinfunction "D2$2_D2$2") (pintype "bidirectional"))
      (node (ref "U$14") (pin "SENSE") (pinfunction "SENSE_SENSE") (pintype "bidirectional"))
    )
    (net (code "61") (name "Net-(R18-Pad1)") (class "Default")
      (node (ref "R18") (pin "1") (pinfunction "1_1") (pintype "passive"))
      (node (ref "U$14") (pin "ON") (pinfunction "ON_ON") (pintype "bidirectional"))
      (node (ref "U$15") (pin "C") (pinfunction "C_C") (pintype "bidirectional"))
    )
    (net (code "62") (name "Net-(R21-Pad2)") (class "Default")
      (node (ref "R21") (pin "2") (pinfunction "2_2") (pintype "passive"))
      (node (ref "U$18") (pin "C") (pinfunction "C_C") (pintype "bidirectional"))
    )
    (net (code "63") (name "Net-(R23-Pad2)") (class "Default")
      (node (ref "R23") (pin "2") (pinfunction "2_2") (pintype "passive"))
      (node (ref "U$21") (pin "C") (pinfunction "C_C") (pintype "bidirectional"))
    )
    (net (code "64") (name "Net-(R24-Pad2)") (class "Default")
      (node (ref "R24") (pin "2") (pinfunction "2_2") (pintype "passive"))
      (node (ref "U$23") (pin "C") (pinfunction "C_C") (pintype "bidirectional"))
    )
    (net (code "65") (name "Net-(R25-Pad2)") (class "Default")
      (node (ref "R25") (pin "2") (pinfunction "2_2") (pintype "passive"))
      (node (ref "U$24") (pin "C") (pinfunction "C_C") (pintype "bidirectional"))
    )
    (net (code "66") (name "Net-(R26-Pad2)") (class "Default")
      (node (ref "R26") (pin "2") (pinfunction "2_2") (pintype "passive"))
      (node (ref "U$25") (pin "C") (pinfunction "C_C") (pintype "bidirectional"))
    )
    (net (code "67") (name "Net-(U$2-Pad3:1PPS)") (class "Default")
      (node (ref "U$2") (pin "3:1PPS") (pinfunction "3:1PPS_3:1PPS") (pintype "bidirectional"))
      (node (ref "U$3") (pin "B1") (pinfunction "B1_B1") (pintype "bidirectional"))
    )
    (net (code "68") (name "Net-(U$2-Pad11:RF_IN)") (class "Default")
      (node (ref "U$2") (pin "11:RF_IN") (pinfunction "11:RF_IN_11:RF_IN") (pintype "bidirectional"))
      (node (ref "U$5") (pin "SIG") (pinfunction "SIG_SIG") (pintype "bidirectional"))
    )
    (net (code "69") (name "Net-(U$3-PadC2)") (class "Default")
      (node (ref "U$3") (pin "C2") (pinfunction "C2_C2") (pintype "bidirectional"))
      (node (ref "U$4") (pin "C") (pinfunction "C_C") (pintype "bidirectional"))
    )
    (net (code "70") (name "Net-(U$7-PadS1)") (class "Default")
      (node (ref "U$7") (pin "S1") (pinfunction "S1_S1") (pintype "bidirectional"))
      (node (ref "U$7") (pin "S2") (pinfunction "S2_S2") (pintype "bidirectional"))
    )
    (net (code "71") (name "Net-(U$10-PadS1)") (class "Default")
      (node (ref "U$10") (pin "S1") (pinfunction "S1_S1") (pintype "bidirectional"))
      (node (ref "U$10") (pin "S2") (pinfunction "S2_S2") (pintype "bidirectional"))
    )
    (net (code "72") (name "Net-(U$13-PadS1)") (class "Default")
      (node (ref "U$13") (pin "S1") (pinfunction "S1_S1") (pintype "bidirectional"))
      (node (ref "U$13") (pin "S2") (pinfunction "S2_S2") (pintype "bidirectional"))
    )
    (net (code "73") (name "Net-(U2-RD7{slash}PSP7)") (class "Default")
      (node (ref "R2") (pin "1") (pinfunction "1_1") (pintype "passive"))
      (node (ref "U$1") (pin "S#") (pinfunction "S#_S#") (pintype "bidirectional"))
      (node (ref "U2") (pin "5") (pinfunction "RD7/PSP7_5") (pintype "bidirectional"))
    )
    (net (code "74") (name "unconnected-(U$1-PadDNU$4)") (class "Default")
      (node (ref "U$1") (pin "DNU$4") (pinfunction "DNU$4_DNU$4") (pintype "bidirectional"))
    )
    (net (code "75") (name "unconnected-(U$1-PadDNU$5)") (class "Default")
      (node (ref "U$1") (pin "DNU$5") (pinfunction "DNU$5_DNU$5") (pintype "bidirectional"))
    )
    (net (code "76") (name "unconnected-(U$1-PadDNU$6)") (class "Default")
      (node (ref "U$1") (pin "DNU$6") (pinfunction "DNU$6_DNU$6") (pintype "bidirectional"))
    )
    (net (code "77") (name "unconnected-(U$1-PadDNU$11)") (class "Default")
      (node (ref "U$1") (pin "DNU$11") (pinfunction "DNU$11_DNU$11") (pintype "bidirectional"))
    )
    (net (code "78") (name "unconnected-(U$1-PadDNU$12)") (class "Default")
      (node (ref "U$1") (pin "DNU$12") (pinfunction "DNU$12_DNU$12") (pintype "bidirectional"))
    )
    (net (code "79") (name "unconnected-(U$1-PadDNU$13)") (class "Default")
      (node (ref "U$1") (pin "DNU$13") (pinfunction "DNU$13_DNU$13") (pintype "bidirectional"))
    )
    (net (code "80") (name "unconnected-(U$1-PadDNU$14)") (class "Default")
      (node (ref "U$1") (pin "DNU$14") (pinfunction "DNU$14_DNU$14") (pintype "bidirectional"))
    )
    (net (code "81") (name "unconnected-(U$1-PadDQ3{slash}HOLD#)") (class "Default")
      (node (ref "U$1") (pin "DQ3/HOLD#") (pinfunction "DQ3/HOLD#_DQ3/HOLD#") (pintype "bidirectional"))
    )
    (net (code "82") (name "unconnected-(U$1-PadRESET#)") (class "Default")
      (node (ref "U$1") (pin "RESET#") (pinfunction "RESET#_RESET#") (pintype "bidirectional"))
    )
    (net (code "83") (name "unconnected-(U$1-PadW#{slash}DQ2)") (class "Default")
      (node (ref "U$1") (pin "W#/DQ2") (pinfunction "W#/DQ2_W#/DQ2") (pintype "bidirectional"))
    )
    (net (code "84") (name "unconnected-(U$2-Pad1:BOOT_SEL)") (class "Default")
      (node (ref "U$2") (pin "1:BOOT_SEL") (pinfunction "1:BOOT_SEL_1:BOOT_SEL") (pintype "bidirectional"))
    )
    (net (code "85") (name "unconnected-(U$2-Pad2:SPI_MISO)") (class "Default")
      (node (ref "U$2") (pin "2:SPI_MISO") (pinfunction "2:SPI_MISO_2:SPI_MISO") (pintype "bidirectional"))
    )
    (net (code "86") (name "unconnected-(U$2-Pad4:NC)") (class "Default")
      (node (ref "U$2") (pin "4:NC") (pinfunction "4:NC_4:NC") (pintype "bidirectional"))
    )
    (net (code "87") (name "unconnected-(U$2-Pad5:NC)") (class "Default")
      (node (ref "U$2") (pin "5:NC") (pinfunction "5:NC_5:NC") (pintype "bidirectional"))
    )
    (net (code "88") (name "unconnected-(U$2-Pad6:NC)") (class "Default")
      (node (ref "U$2") (pin "6:NC") (pinfunction "6:NC_6:NC") (pintype "bidirectional"))
    )
    (net (code "89") (name "unconnected-(U$2-Pad7:NC)") (class "Default")
      (node (ref "U$2") (pin "7:NC") (pinfunction "7:NC_7:NC") (pintype "bidirectional"))
    )
    (net (code "90") (name "unconnected-(U$2-Pad8:RSTN)") (class "Default")
      (node (ref "U$2") (pin "8:RSTN") (pinfunction "8:RSTN_8:RSTN") (pintype "bidirectional"))
    )
    (net (code "91") (name "unconnected-(U$2-Pad9:SPI_CSN)") (class "Default")
      (node (ref "U$2") (pin "9:SPI_CSN") (pinfunction "9:SPI_CSN_9:SPI_CSN") (pintype "bidirectional"))
    )
    (net (code "92") (name "unconnected-(U$2-Pad14:SPI_MOSI)") (class "Default")
      (node (ref "U$2") (pin "14:SPI_MOSI") (pinfunction "14:SPI_MOSI_14:SPI_MOSI") (pintype "bidirectional"))
    )
    (net (code "93") (name "unconnected-(U$2-Pad15:NC)") (class "Default")
      (node (ref "U$2") (pin "15:NC") (pinfunction "15:NC_15:NC") (pintype "bidirectional"))
    )
    (net (code "94") (name "unconnected-(U$2-Pad16:SPI_CLK)") (class "Default")
      (node (ref "U$2") (pin "16:SPI_CLK") (pinfunction "16:SPI_CLK_16:SPI_CLK") (pintype "bidirectional"))
    )
    (net (code "95") (name "unconnected-(U$2-Pad17:NC)") (class "Default")
      (node (ref "U$2") (pin "17:NC") (pinfunction "17:NC_17:NC") (pintype "bidirectional"))
    )
    (net (code "96") (name "unconnected-(U$2-Pad18:SDA)") (class "Default")
      (node (ref "U$2") (pin "18:SDA") (pinfunction "18:SDA_18:SDA") (pintype "bidirectional"))
    )
    (net (code "97") (name "unconnected-(U$2-Pad19:SCL)") (class "Default")
      (node (ref "U$2") (pin "19:SCL") (pinfunction "19:SCL_19:SCL") (pintype "bidirectional"))
    )
    (net (code "98") (name "unconnected-(U$6-NC-PadNC1)") (class "Default")
      (node (ref "U$6") (pin "NC1") (pinfunction "NC_NC1") (pintype "bidirectional"))
    )
    (net (code "99") (name "unconnected-(U$6-PadCH1)") (class "Default")
      (node (ref "U$6") (pin "CH1") (pinfunction "CH1_CH1") (pintype "bidirectional"))
    )
    (net (code "100") (name "unconnected-(U$6-PadCH2)") (class "Default")
      (node (ref "U$6") (pin "CH2") (pinfunction "CH2_CH2") (pintype "bidirectional"))
    )
    (net (code "101") (name "unconnected-(U$6-PadCH3)") (class "Default")
      (node (ref "U$6") (pin "CH3") (pinfunction "CH3_CH3") (pintype "bidirectional"))
    )
    (net (code "102") (name "unconnected-(U$6-PadNC2)") (class "Default")
      (node (ref "U$6") (pin "NC2") (pinfunction "NC2_NC2") (pintype "bidirectional"))
    )
    (net (code "103") (name "unconnected-(U$8-PadPWRGD)") (class "Default")
      (node (ref "U$8") (pin "PWRGD") (pinfunction "PWRGD_PWRGD") (pintype "bidirectional"))
    )
    (net (code "104") (name "unconnected-(U$11-PadPWRGD)") (class "Default")
      (node (ref "U$11") (pin "PWRGD") (pinfunction "PWRGD_PWRGD") (pintype "bidirectional"))
    )
    (net (code "105") (name "unconnected-(U$14-PadPWRGD)") (class "Default")
      (node (ref "U$14") (pin "PWRGD") (pinfunction "PWRGD_PWRGD") (pintype "bidirectional"))
    )
    (net (code "106") (name "unconnected-(U$19-NIC-PadNIC@1)") (class "Default")
      (node (ref "U$19") (pin "NIC@1") (pinfunction "NIC_NIC@1") (pintype "bidirectional"))
    )
    (net (code "107") (name "unconnected-(U$19-NIC-PadNIC@2)") (class "Default")
      (node (ref "U$19") (pin "NIC@2") (pinfunction "NIC_NIC@2") (pintype "bidirectional"))
    )
    (net (code "108") (name "unconnected-(U2-RA4{slash}T0CKI-Pad23)") (class "Default")
      (node (ref "U2") (pin "23") (pinfunction "RA4/T0CKI_23") (pintype "bidirectional"))
    )
    (net (code "109") (name "unconnected-(U2-RA5{slash}AN4{slash}SS*-Pad24)") (class "Default")
      (node (ref "U2") (pin "24") (pinfunction "RA5/AN4/SS*_24") (pintype "bidirectional"))
    )
    (net (code "110") (name "unconnected-(U2-RB3{slash}PGM-Pad11)") (class "Default")
      (node (ref "U2") (pin "11") (pinfunction "RB3/PGM_11") (pintype "bidirectional"))
    )
    (net (code "111") (name "unconnected-(U2-RC1{slash}T1OSI{slash}CCP2-Pad35)") (class "Default")
      (node (ref "U2") (pin "35") (pinfunction "RC1/T1OSI/CCP2_35") (pintype "bidirectional"))
    )
    (net (code "112") (name "unconnected-(U2-RC2{slash}CCP1-Pad36)") (class "Default")
      (node (ref "U2") (pin "36") (pinfunction "RC2/CCP1_36") (pintype "bidirectional"))
    )
    (net (code "113") (name "unconnected-(U2-RD0{slash}PSP0-Pad38)") (class "Default")
      (node (ref "U2") (pin "38") (pinfunction "RD0/PSP0_38") (pintype "bidirectional"))
    )
    (net (code "114") (name "unconnected-(U2-RD3{slash}PSP3-Pad41)") (class "Default")
      (node (ref "U2") (pin "41") (pinfunction "RD3/PSP3_41") (pintype "bidirectional"))
    )
    (net (code "115") (name "unconnected-(U2-RE0{slash}RD*{slash}AN5-Pad25)") (class "Default")
      (node (ref "U2") (pin "25") (pinfunction "RE0/RD*/AN5_25") (pintype "bidirectional"))
    )
    (net (code "116") (name "unconnected-(U2-RE1{slash}WR*{slash}AN6-Pad26)") (class "Default")
      (node (ref "U2") (pin "26") (pinfunction "RE1/WR*/AN6_26") (pintype "bidirectional"))
    )
    (net (code "117") (name "unconnected-(U2-RE2{slash}CS*{slash}AN7-Pad27)") (class "Default")
      (node (ref "U2") (pin "27") (pinfunction "RE2/CS*/AN7_27") (pintype "bidirectional"))
    )
  )
)
